# M700A.net
KiCad netlist of a schematic drawn in EAGLE
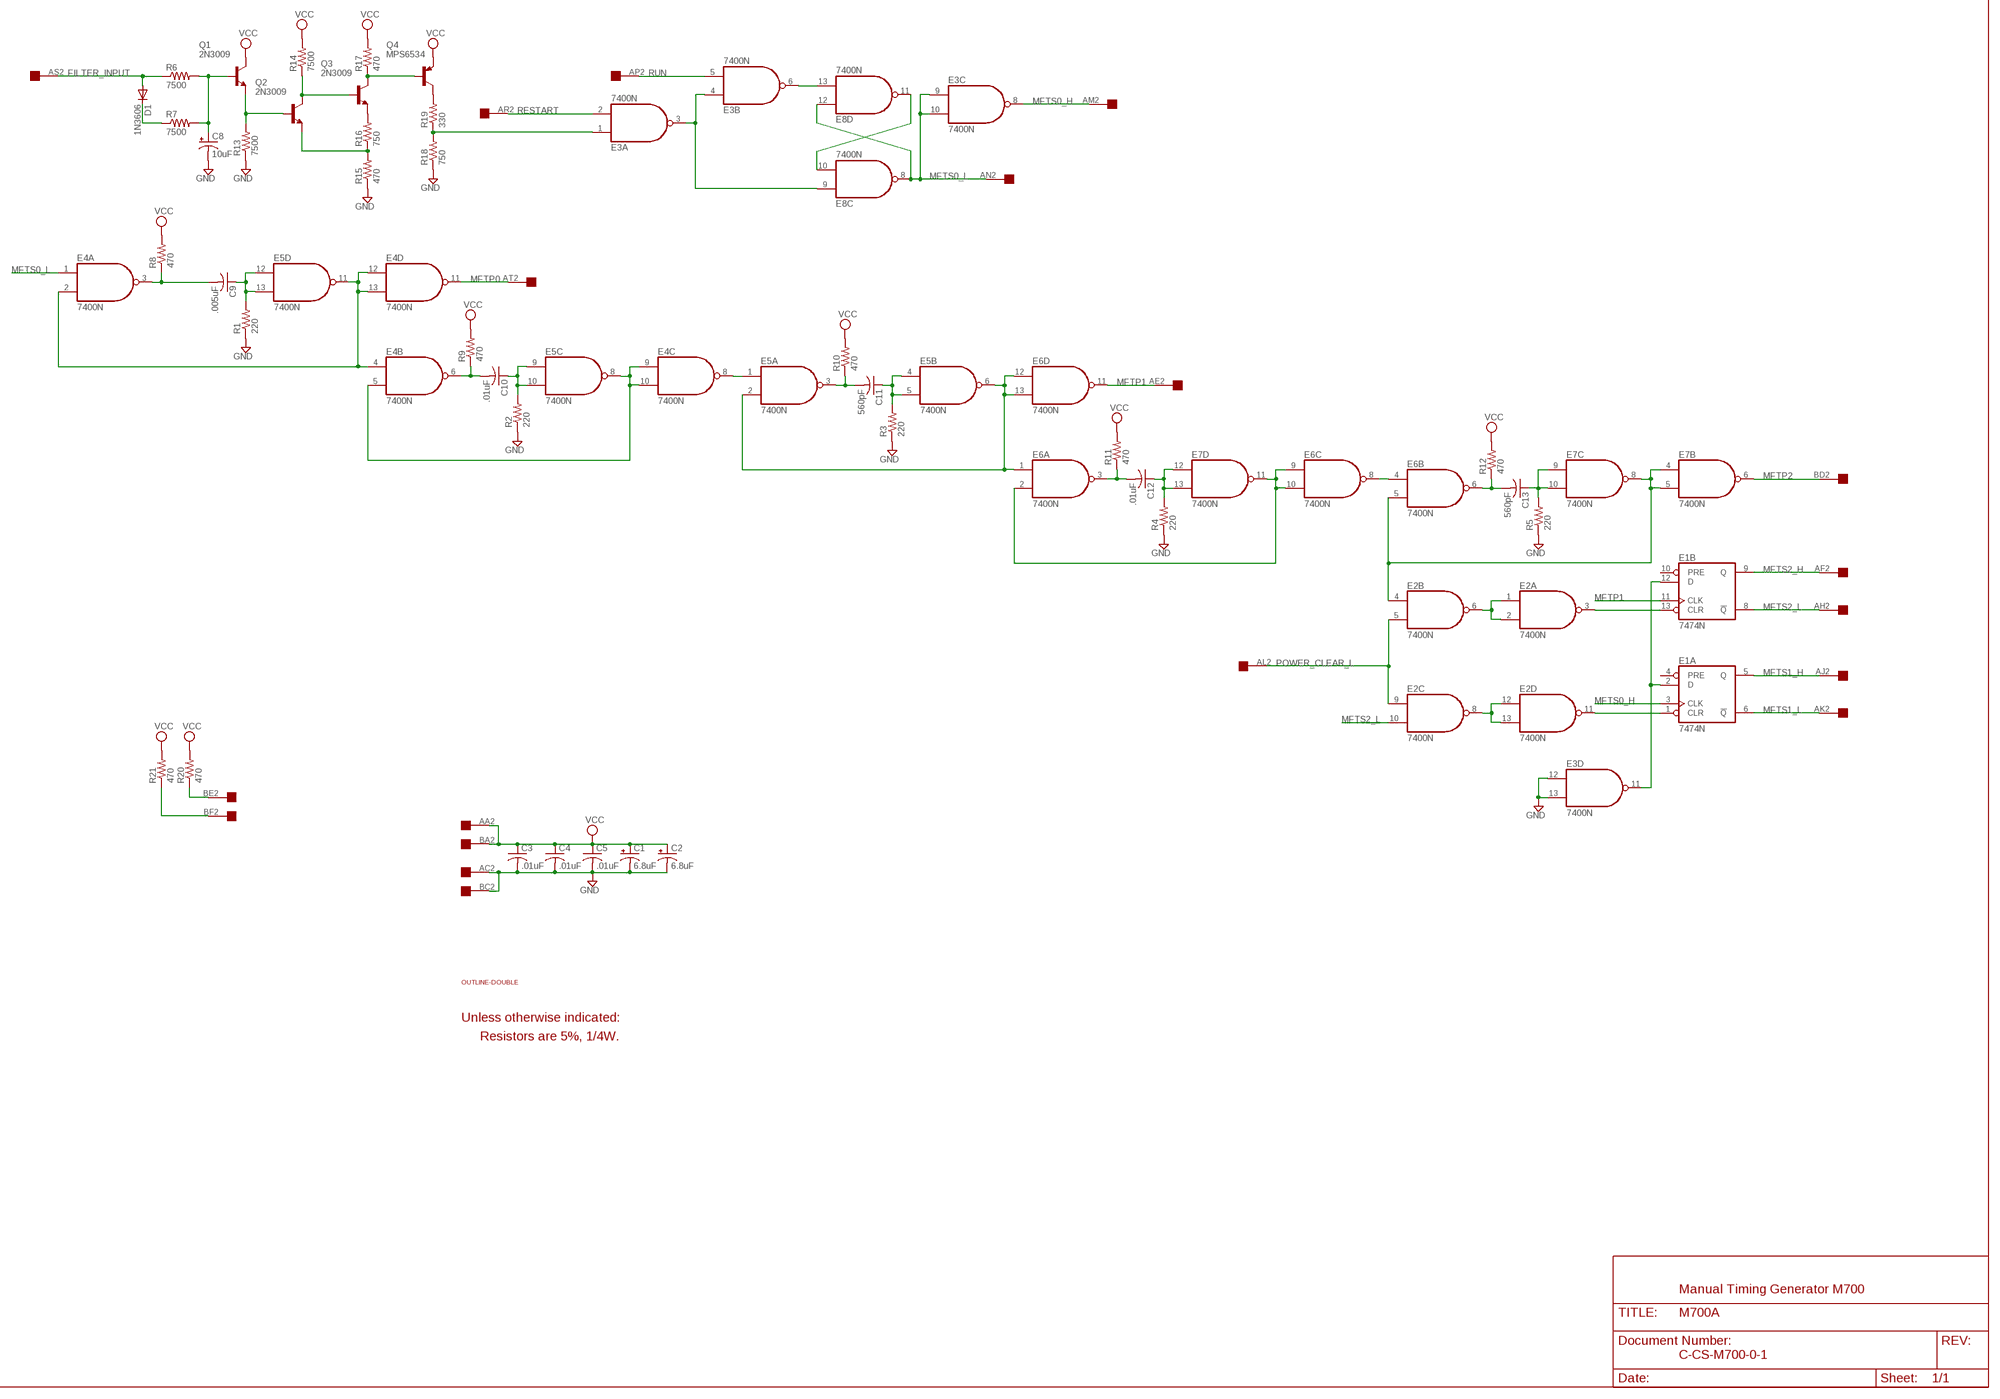
[diagram p0: schematic, sheet 1]

(export (version "E")
  (design (tool "Eeschema 10.0.6"))
  (components
    (comp (ref "C1")
      (value "6.8uF")
      (footprint "eagle-import:E15-5")
      (libsource (lib "eagle-import") (part "CPOL-USE15-5AXIAL"))
    )
    (comp (ref "C2")
      (value "6.8uF")
      (footprint "eagle-import:E15-5")
      (libsource (lib "eagle-import") (part "CPOL-USE15-5AXIAL"))
    )
    (comp (ref "C3")
      (value ".01uF")
      (footprint "eagle-import:C050-025X075")
      (libsource (lib "eagle-import") (part "C-US050-025X075"))
    )
    (comp (ref "C4")
      (value ".01uF")
      (footprint "eagle-import:C050-025X075")
      (libsource (lib "eagle-import") (part "C-US050-025X075"))
    )
    (comp (ref "C5")
      (value ".01uF")
      (footprint "eagle-import:C050-025X075")
      (libsource (lib "eagle-import") (part "C-US050-025X075"))
    )
    (comp (ref "C8")
      (value "10uF")
      (footprint "eagle-import:E15-5")
      (libsource (lib "eagle-import") (part "CPOL-USE15-5AXIAL"))
    )
    (comp (ref "C9")
      (value ".005uF")
      (footprint "eagle-import:C050-025X075")
      (libsource (lib "eagle-import") (part "C-US050-025X075"))
    )
    (comp (ref "C10")
      (value ".01uF")
      (footprint "eagle-import:C050-025X075")
      (libsource (lib "eagle-import") (part "C-US050-025X075"))
    )
    (comp (ref "C11")
      (value "560pF")
      (footprint "eagle-import:C050-025X075")
      (libsource (lib "eagle-import") (part "C-US050-025X075"))
    )
    (comp (ref "C12")
      (value ".01uF")
      (footprint "eagle-import:C050-025X075")
      (libsource (lib "eagle-import") (part "C-US050-025X075"))
    )
    (comp (ref "C13")
      (value "560pF")
      (footprint "eagle-import:C050-025X075")
      (libsource (lib "eagle-import") (part "C-US050-025X075"))
    )
    (comp (ref "D1")
      (value "1N3606")
      (footprint "eagle-import:DO35-10")
      (libsource (lib "eagle-import") (part "1N4148DO35-10"))
    )
    (comp (ref "E1")
      (value "7474N")
      (footprint "eagle-import:DIL14")
      (libsource (lib "eagle-import") (part "7474NS"))
    )
    (comp (ref "E2")
      (value "7400N")
      (footprint "eagle-import:DIL14")
      (libsource (lib "eagle-import") (part "7400N"))
    )
    (comp (ref "E3")
      (value "7400N")
      (footprint "eagle-import:DIL14")
      (libsource (lib "eagle-import") (part "7400N"))
    )
    (comp (ref "E4")
      (value "7400N")
      (footprint "eagle-import:DIL14")
      (libsource (lib "eagle-import") (part "7400N"))
    )
    (comp (ref "E5")
      (value "7400N")
      (footprint "eagle-import:DIL14")
      (libsource (lib "eagle-import") (part "7400N"))
    )
    (comp (ref "E6")
      (value "7400N")
      (footprint "eagle-import:DIL14")
      (libsource (lib "eagle-import") (part "7400N"))
    )
    (comp (ref "E7")
      (value "7400N")
      (footprint "eagle-import:DIL14")
      (libsource (lib "eagle-import") (part "7400N"))
    )
    (comp (ref "E8")
      (value "7400N")
      (footprint "eagle-import:DIL14")
      (libsource (lib "eagle-import") (part "7400N"))
    )
    (comp (ref "Q1")
      (value "2N3009")
      (footprint "eagle-import:TO5")
      (libsource (lib "eagle-import") (part "2N2102"))
    )
    (comp (ref "Q2")
      (value "2N3009")
      (footprint "eagle-import:TO5")
      (libsource (lib "eagle-import") (part "2N2102"))
    )
    (comp (ref "Q3")
      (value "2N3009")
      (footprint "eagle-import:TO5")
      (libsource (lib "eagle-import") (part "2N2102"))
    )
    (comp (ref "Q4")
      (value "MPS6534")
      (footprint "eagle-import:TO5")
      (libsource (lib "eagle-import") (part "2N2905"))
    )
    (comp (ref "R1")
      (value "220")
      (footprint "eagle-import:0207_10")
      (libsource (lib "eagle-import") (part "R-US_0207/10"))
    )
    (comp (ref "R2")
      (value "220")
      (footprint "eagle-import:0207_10")
      (libsource (lib "eagle-import") (part "R-US_0207/10"))
    )
    (comp (ref "R3")
      (value "220")
      (footprint "eagle-import:0207_10")
      (libsource (lib "eagle-import") (part "R-US_0207/10"))
    )
    (comp (ref "R4")
      (value "220")
      (footprint "eagle-import:0207_10")
      (libsource (lib "eagle-import") (part "R-US_0207/10"))
    )
    (comp (ref "R5")
      (value "220")
      (footprint "eagle-import:0207_10")
      (libsource (lib "eagle-import") (part "R-US_0207/10"))
    )
    (comp (ref "R6")
      (value "7500")
      (footprint "eagle-import:0207_10")
      (libsource (lib "eagle-import") (part "R-US_0207/10"))
    )
    (comp (ref "R7")
      (value "7500")
      (footprint "eagle-import:0207_10")
      (libsource (lib "eagle-import") (part "R-US_0207/10"))
    )
    (comp (ref "R8")
      (value "470")
      (footprint "eagle-import:0207_10")
      (libsource (lib "eagle-import") (part "R-US_0207/10"))
    )
    (comp (ref "R9")
      (value "470")
      (footprint "eagle-import:0207_10")
      (libsource (lib "eagle-import") (part "R-US_0207/10"))
    )
    (comp (ref "R10")
      (value "470")
      (footprint "eagle-import:0207_10")
      (libsource (lib "eagle-import") (part "R-US_0207/10"))
    )
    (comp (ref "R11")
      (value "470")
      (footprint "eagle-import:0207_10")
      (libsource (lib "eagle-import") (part "R-US_0207/10"))
    )
    (comp (ref "R12")
      (value "470")
      (footprint "eagle-import:0207_10")
      (libsource (lib "eagle-import") (part "R-US_0207/10"))
    )
    (comp (ref "R13")
      (value "7500")
      (footprint "eagle-import:0207_10")
      (libsource (lib "eagle-import") (part "R-US_0207/10"))
    )
    (comp (ref "R14")
      (value "7500")
      (footprint "eagle-import:0207_10")
      (libsource (lib "eagle-import") (part "R-US_0207/10"))
    )
    (comp (ref "R15")
      (value "470")
      (footprint "eagle-import:0207_10")
      (libsource (lib "eagle-import") (part "R-US_0207/10"))
    )
    (comp (ref "R16")
      (value "750")
      (footprint "eagle-import:0207_10")
      (libsource (lib "eagle-import") (part "R-US_0207/10"))
    )
    (comp (ref "R17")
      (value "470")
      (footprint "eagle-import:0207_10")
      (libsource (lib "eagle-import") (part "R-US_0207/10"))
    )
    (comp (ref "R18")
      (value "750")
      (footprint "eagle-import:0207_10")
      (libsource (lib "eagle-import") (part "R-US_0207/10"))
    )
    (comp (ref "R19")
      (value "330")
      (footprint "eagle-import:0207_10")
      (libsource (lib "eagle-import") (part "R-US_0207/10"))
    )
    (comp (ref "R20")
      (value "470")
      (footprint "eagle-import:0207_10")
      (libsource (lib "eagle-import") (part "R-US_0207/10"))
    )
    (comp (ref "R21")
      (value "470")
      (footprint "eagle-import:0207_10")
      (libsource (lib "eagle-import") (part "R-US_0207/10"))
    )
    (comp (ref "U$1")
      (value "DOUBLE")
      (footprint "eagle-import:EDGE-CON4")
      (libsource (lib "eagle-import") (part "DOUBLE"))
    )
    (comp (ref "U$2")
      (value "OUTLINE-DOUBLE")
      (footprint "eagle-import:DOUBLE")
      (libsource (lib "eagle-import") (part "OUTLINE-DOUBLE"))
    )
  )
  (nets
    (net (code "1") (name "/FILTER_INPUT") (class "Default")
      (node (ref "D1") (pin "A") (pinfunction "A_A") (pintype "passive"))
      (node (ref "R6") (pin "1") (pinfunction "1_1") (pintype "passive"))
      (node (ref "U$1") (pin "AS2") (pinfunction "1_AS2") (pintype "bidirectional"))
    )
    (net (code "2") (name "/MFTP0") (class "Default")
      (node (ref "E4") (pin "11") (pinfunction "O_11") (pintype "output"))
      (node (ref "U$1") (pin "AT2") (pinfunction "1_AT2") (pintype "bidirectional"))
    )
    (net (code "3") (name "/MFTP1") (class "Default")
      (node (ref "E1") (pin "11") (pinfunction "CLK_11") (pintype "input"))
      (node (ref "E6") (pin "11") (pinfunction "O_11") (pintype "output"))
      (node (ref "U$1") (pin "AE2") (pinfunction "1_AE2") (pintype "bidirectional"))
    )
    (net (code "4") (name "/MFTP2") (class "Default")
      (node (ref "E7") (pin "6") (pinfunction "O_6") (pintype "output"))
      (node (ref "U$1") (pin "BD2") (pinfunction "1_BD2") (pintype "bidirectional"))
    )
    (net (code "5") (name "/MFTS0_H") (class "Default")
      (node (ref "E1") (pin "3") (pinfunction "CLK_3") (pintype "input"))
      (node (ref "E3") (pin "8") (pinfunction "O_8") (pintype "output"))
      (node (ref "U$1") (pin "AM2") (pinfunction "1_AM2") (pintype "bidirectional"))
    )
    (net (code "6") (name "/MFTS0_L") (class "Default")
      (node (ref "E3") (pin "10") (pinfunction "I1_10") (pintype "input"))
      (node (ref "E3") (pin "9") (pinfunction "I0_9") (pintype "input"))
      (node (ref "E4") (pin "1") (pinfunction "I0_1") (pintype "input"))
      (node (ref "E8") (pin "12") (pinfunction "I0_12") (pintype "input"))
      (node (ref "E8") (pin "8") (pinfunction "O_8") (pintype "output"))
      (node (ref "U$1") (pin "AN2") (pinfunction "1_AN2") (pintype "bidirectional"))
    )
    (net (code "7") (name "/MFTS1_H") (class "Default")
      (node (ref "E1") (pin "5") (pinfunction "Q_5") (pintype "output"))
      (node (ref "U$1") (pin "AJ2") (pinfunction "1_AJ2") (pintype "bidirectional"))
    )
    (net (code "8") (name "/MFTS1_L") (class "Default")
      (node (ref "E1") (pin "6") (pinfunction "~{Q}_6") (pintype "output"))
      (node (ref "U$1") (pin "AK2") (pinfunction "1_AK2") (pintype "bidirectional"))
    )
    (net (code "9") (name "/MFTS2_H") (class "Default")
      (node (ref "E1") (pin "9") (pinfunction "Q_9") (pintype "output"))
      (node (ref "U$1") (pin "AF2") (pinfunction "1_AF2") (pintype "bidirectional"))
    )
    (net (code "10") (name "/MFTS2_L") (class "Default")
      (node (ref "E1") (pin "8") (pinfunction "~{Q}_8") (pintype "output"))
      (node (ref "E2") (pin "10") (pinfunction "I1_10") (pintype "input"))
      (node (ref "U$1") (pin "AH2") (pinfunction "1_AH2") (pintype "bidirectional"))
    )
    (net (code "11") (name "/POWER_CLEAR_L") (class "Default")
      (node (ref "E2") (pin "5") (pinfunction "I1_5") (pintype "input"))
      (node (ref "E2") (pin "9") (pinfunction "I0_9") (pintype "input"))
      (node (ref "U$1") (pin "AL2") (pinfunction "1_AL2") (pintype "bidirectional"))
    )
    (net (code "12") (name "/RESTART") (class "Default")
      (node (ref "E3") (pin "2") (pinfunction "I1_2") (pintype "input"))
      (node (ref "U$1") (pin "AR2") (pinfunction "1_AR2") (pintype "bidirectional"))
    )
    (net (code "13") (name "/RUN") (class "Default")
      (node (ref "E3") (pin "5") (pinfunction "I1_5") (pintype "input"))
      (node (ref "U$1") (pin "AP2") (pinfunction "1_AP2") (pintype "bidirectional"))
    )
    (net (code "14") (name "GND") (class "Default")
      (node (ref "C1") (pin "-") (pinfunction "-_-") (pintype "passive"))
      (node (ref "C2") (pin "-") (pinfunction "-_-") (pintype "passive"))
      (node (ref "C3") (pin "2") (pinfunction "2_2") (pintype "passive"))
      (node (ref "C4") (pin "2") (pinfunction "2_2") (pintype "passive"))
      (node (ref "C5") (pin "2") (pinfunction "2_2") (pintype "passive"))
      (node (ref "C8") (pin "-") (pinfunction "-_-") (pintype "passive"))
      (node (ref "E3") (pin "12") (pinfunction "I0_12") (pintype "input"))
      (node (ref "E3") (pin "13") (pinfunction "I1_13") (pintype "input"))
      (node (ref "R1") (pin "1") (pinfunction "1_1") (pintype "passive"))
      (node (ref "R13") (pin "1") (pinfunction "1_1") (pintype "passive"))
      (node (ref "R15") (pin "1") (pinfunction "1_1") (pintype "passive"))
      (node (ref "R18") (pin "1") (pinfunction "1_1") (pintype "passive"))
      (node (ref "R2") (pin "1") (pinfunction "1_1") (pintype "passive"))
      (node (ref "R3") (pin "1") (pinfunction "1_1") (pintype "passive"))
      (node (ref "R4") (pin "1") (pinfunction "1_1") (pintype "passive"))
      (node (ref "R5") (pin "1") (pinfunction "1_1") (pintype "passive"))
      (node (ref "U$1") (pin "AC2") (pinfunction "1_AC2") (pintype "bidirectional"))
      (node (ref "U$1") (pin "BC2") (pinfunction "1_BC2") (pintype "bidirectional"))
    )
    (net (code "15") (name "Net-(D1-PadC)") (class "Default")
      (node (ref "D1") (pin "C") (pinfunction "C_C") (pintype "passive"))
      (node (ref "R7") (pin "1") (pinfunction "1_1") (pintype "passive"))
    )
    (net (code "16") (name "Net-(E1A-CLR)") (class "Default")
      (node (ref "E1") (pin "1") (pinfunction "CLR_1") (pintype "input"))
      (node (ref "E2") (pin "11") (pinfunction "O_11") (pintype "output"))
    )
    (net (code "17") (name "Net-(E1A-D)") (class "Default")
      (node (ref "E1") (pin "12") (pinfunction "D_12") (pintype "input"))
      (node (ref "E1") (pin "2") (pinfunction "D_2") (pintype "input"))
      (node (ref "E3") (pin "11") (pinfunction "O_11") (pintype "output"))
    )
    (net (code "18") (name "Net-(E1B-CLR)") (class "Default")
      (node (ref "E1") (pin "13") (pinfunction "CLR_13") (pintype "input"))
      (node (ref "E2") (pin "3") (pinfunction "O_3") (pintype "output"))
    )
    (net (code "19") (name "Net-(E2A-I0)") (class "Default")
      (node (ref "E2") (pin "1") (pinfunction "I0_1") (pintype "input"))
      (node (ref "E2") (pin "2") (pinfunction "I1_2") (pintype "input"))
      (node (ref "E2") (pin "6") (pinfunction "O_6") (pintype "output"))
    )
    (net (code "20") (name "Net-(E2B-I0)") (class "Default")
      (node (ref "E2") (pin "4") (pinfunction "I0_4") (pintype "input"))
      (node (ref "E6") (pin "5") (pinfunction "I1_5") (pintype "input"))
      (node (ref "E7") (pin "4") (pinfunction "I0_4") (pintype "input"))
      (node (ref "E7") (pin "5") (pinfunction "I1_5") (pintype "input"))
      (node (ref "E7") (pin "8") (pinfunction "O_8") (pintype "output"))
    )
    (net (code "21") (name "Net-(E2C-O)") (class "Default")
      (node (ref "E2") (pin "12") (pinfunction "I0_12") (pintype "input"))
      (node (ref "E2") (pin "13") (pinfunction "I1_13") (pintype "input"))
      (node (ref "E2") (pin "8") (pinfunction "O_8") (pintype "output"))
    )
    (net (code "22") (name "Net-(E3A-I0)") (class "Default")
      (node (ref "E3") (pin "1") (pinfunction "I0_1") (pintype "input"))
      (node (ref "R18") (pin "2") (pinfunction "2_2") (pintype "passive"))
      (node (ref "R19") (pin "1") (pinfunction "1_1") (pintype "passive"))
    )
    (net (code "23") (name "Net-(E3A-O)") (class "Default")
      (node (ref "E3") (pin "3") (pinfunction "O_3") (pintype "output"))
      (node (ref "E3") (pin "4") (pinfunction "I0_4") (pintype "input"))
      (node (ref "E8") (pin "9") (pinfunction "I0_9") (pintype "input"))
    )
    (net (code "24") (name "Net-(E3B-O)") (class "Default")
      (node (ref "E3") (pin "6") (pinfunction "O_6") (pintype "output"))
      (node (ref "E8") (pin "13") (pinfunction "I1_13") (pintype "input"))
    )
    (net (code "25") (name "Net-(E4A-I1)") (class "Default")
      (node (ref "E4") (pin "12") (pinfunction "I0_12") (pintype "input"))
      (node (ref "E4") (pin "13") (pinfunction "I1_13") (pintype "input"))
      (node (ref "E4") (pin "2") (pinfunction "I1_2") (pintype "input"))
      (node (ref "E4") (pin "4") (pinfunction "I0_4") (pintype "input"))
      (node (ref "E5") (pin "11") (pinfunction "O_11") (pintype "output"))
    )
    (net (code "26") (name "Net-(E4A-O)") (class "Default")
      (node (ref "C9") (pin "2") (pinfunction "2_2") (pintype "passive"))
      (node (ref "E4") (pin "3") (pinfunction "O_3") (pintype "output"))
      (node (ref "R8") (pin "1") (pinfunction "1_1") (pintype "passive"))
    )
    (net (code "27") (name "Net-(E4B-I1)") (class "Default")
      (node (ref "E4") (pin "10") (pinfunction "I1_10") (pintype "input"))
      (node (ref "E4") (pin "5") (pinfunction "I1_5") (pintype "input"))
      (node (ref "E4") (pin "9") (pinfunction "I0_9") (pintype "input"))
      (node (ref "E5") (pin "8") (pinfunction "O_8") (pintype "output"))
    )
    (net (code "28") (name "Net-(E4B-O)") (class "Default")
      (node (ref "C10") (pin "2") (pinfunction "2_2") (pintype "passive"))
      (node (ref "E4") (pin "6") (pinfunction "O_6") (pintype "output"))
      (node (ref "R9") (pin "1") (pinfunction "1_1") (pintype "passive"))
    )
    (net (code "29") (name "Net-(E4C-O)") (class "Default")
      (node (ref "E4") (pin "8") (pinfunction "O_8") (pintype "output"))
      (node (ref "E5") (pin "1") (pinfunction "I0_1") (pintype "input"))
    )
    (net (code "30") (name "Net-(E5A-I1)") (class "Default")
      (node (ref "E5") (pin "2") (pinfunction "I1_2") (pintype "input"))
      (node (ref "E5") (pin "6") (pinfunction "O_6") (pintype "output"))
      (node (ref "E6") (pin "1") (pinfunction "I0_1") (pintype "input"))
      (node (ref "E6") (pin "12") (pinfunction "I0_12") (pintype "input"))
      (node (ref "E6") (pin "13") (pinfunction "I1_13") (pintype "input"))
    )
    (net (code "31") (name "Net-(E5A-O)") (class "Default")
      (node (ref "C11") (pin "2") (pinfunction "2_2") (pintype "passive"))
      (node (ref "E5") (pin "3") (pinfunction "O_3") (pintype "output"))
      (node (ref "R10") (pin "1") (pinfunction "1_1") (pintype "passive"))
    )
    (net (code "32") (name "Net-(E5B-I0)") (class "Default")
      (node (ref "C11") (pin "1") (pinfunction "1_1") (pintype "passive"))
      (node (ref "E5") (pin "4") (pinfunction "I0_4") (pintype "input"))
      (node (ref "E5") (pin "5") (pinfunction "I1_5") (pintype "input"))
      (node (ref "R3") (pin "2") (pinfunction "2_2") (pintype "passive"))
    )
    (net (code "33") (name "Net-(E5C-I0)") (class "Default")
      (node (ref "C10") (pin "1") (pinfunction "1_1") (pintype "passive"))
      (node (ref "E5") (pin "10") (pinfunction "I1_10") (pintype "input"))
      (node (ref "E5") (pin "9") (pinfunction "I0_9") (pintype "input"))
      (node (ref "R2") (pin "2") (pinfunction "2_2") (pintype "passive"))
    )
    (net (code "34") (name "Net-(E5D-I0)") (class "Default")
      (node (ref "C9") (pin "1") (pinfunction "1_1") (pintype "passive"))
      (node (ref "E5") (pin "12") (pinfunction "I0_12") (pintype "input"))
      (node (ref "E5") (pin "13") (pinfunction "I1_13") (pintype "input"))
      (node (ref "R1") (pin "2") (pinfunction "2_2") (pintype "passive"))
    )
    (net (code "35") (name "Net-(E6A-I1)") (class "Default")
      (node (ref "E6") (pin "10") (pinfunction "I1_10") (pintype "input"))
      (node (ref "E6") (pin "2") (pinfunction "I1_2") (pintype "input"))
      (node (ref "E6") (pin "9") (pinfunction "I0_9") (pintype "input"))
      (node (ref "E7") (pin "11") (pinfunction "O_11") (pintype "output"))
    )
    (net (code "36") (name "Net-(E6A-O)") (class "Default")
      (node (ref "C12") (pin "2") (pinfunction "2_2") (pintype "passive"))
      (node (ref "E6") (pin "3") (pinfunction "O_3") (pintype "output"))
      (node (ref "R11") (pin "1") (pinfunction "1_1") (pintype "passive"))
    )
    (net (code "37") (name "Net-(E6B-I0)") (class "Default")
      (node (ref "E6") (pin "4") (pinfunction "I0_4") (pintype "input"))
      (node (ref "E6") (pin "8") (pinfunction "O_8") (pintype "output"))
    )
    (net (code "38") (name "Net-(E6B-O)") (class "Default")
      (node (ref "C13") (pin "2") (pinfunction "2_2") (pintype "passive"))
      (node (ref "E6") (pin "6") (pinfunction "O_6") (pintype "output"))
      (node (ref "R12") (pin "1") (pinfunction "1_1") (pintype "passive"))
    )
    (net (code "39") (name "Net-(E7C-I0)") (class "Default")
      (node (ref "C13") (pin "1") (pinfunction "1_1") (pintype "passive"))
      (node (ref "E7") (pin "10") (pinfunction "I1_10") (pintype "input"))
      (node (ref "E7") (pin "9") (pinfunction "I0_9") (pintype "input"))
      (node (ref "R5") (pin "2") (pinfunction "2_2") (pintype "passive"))
    )
    (net (code "40") (name "Net-(E7D-I0)") (class "Default")
      (node (ref "C12") (pin "1") (pinfunction "1_1") (pintype "passive"))
      (node (ref "E7") (pin "12") (pinfunction "I0_12") (pintype "input"))
      (node (ref "E7") (pin "13") (pinfunction "I1_13") (pintype "input"))
      (node (ref "R4") (pin "2") (pinfunction "2_2") (pintype "passive"))
    )
    (net (code "41") (name "Net-(E8C-I1)") (class "Default")
      (node (ref "E8") (pin "10") (pinfunction "I1_10") (pintype "input"))
      (node (ref "E8") (pin "11") (pinfunction "O_11") (pintype "output"))
    )
    (net (code "42") (name "Net-(Q1-B)") (class "Default")
      (node (ref "C8") (pin "+") (pinfunction "+_+") (pintype "passive"))
      (node (ref "Q1") (pin "2") (pinfunction "B_2") (pintype "passive"))
      (node (ref "R6") (pin "2") (pinfunction "2_2") (pintype "passive"))
      (node (ref "R7") (pin "2") (pinfunction "2_2") (pintype "passive"))
    )
    (net (code "43") (name "Net-(Q1-E)") (class "Default")
      (node (ref "Q1") (pin "1") (pinfunction "E_1") (pintype "passive"))
      (node (ref "Q2") (pin "2") (pinfunction "B_2") (pintype "passive"))
      (node (ref "R13") (pin "2") (pinfunction "2_2") (pintype "passive"))
    )
    (net (code "44") (name "Net-(Q2-C)") (class "Default")
      (node (ref "Q2") (pin "3") (pinfunction "C_3") (pintype "passive"))
      (node (ref "Q3") (pin "2") (pinfunction "B_2") (pintype "passive"))
      (node (ref "R14") (pin "1") (pinfunction "1_1") (pintype "passive"))
    )
    (net (code "45") (name "Net-(Q2-E)") (class "Default")
      (node (ref "Q2") (pin "1") (pinfunction "E_1") (pintype "passive"))
      (node (ref "R15") (pin "2") (pinfunction "2_2") (pintype "passive"))
      (node (ref "R16") (pin "1") (pinfunction "1_1") (pintype "passive"))
    )
    (net (code "46") (name "Net-(Q3-C)") (class "Default")
      (node (ref "Q3") (pin "3") (pinfunction "C_3") (pintype "passive"))
      (node (ref "Q4") (pin "2") (pinfunction "B_2") (pintype "passive"))
      (node (ref "R17") (pin "1") (pinfunction "1_1") (pintype "passive"))
    )
    (net (code "47") (name "Net-(Q3-E)") (class "Default")
      (node (ref "Q3") (pin "1") (pinfunction "E_1") (pintype "passive"))
      (node (ref "R16") (pin "2") (pinfunction "2_2") (pintype "passive"))
    )
    (net (code "48") (name "Net-(Q4-C)") (class "Default")
      (node (ref "Q4") (pin "3") (pinfunction "C_3") (pintype "passive"))
      (node (ref "R19") (pin "2") (pinfunction "2_2") (pintype "passive"))
    )
    (net (code "49") (name "Net-(U$1AT-1)") (class "Default")
      (node (ref "R20") (pin "1") (pinfunction "1_1") (pintype "passive"))
      (node (ref "U$1") (pin "BE2") (pinfunction "1_BE2") (pintype "bidirectional"))
    )
    (net (code "50") (name "Net-(U$1AV-1)") (class "Default")
      (node (ref "R21") (pin "1") (pinfunction "1_1") (pintype "passive"))
      (node (ref "U$1") (pin "BF2") (pinfunction "1_BF2") (pintype "bidirectional"))
    )
    (net (code "51") (name "VCC") (class "Default")
      (node (ref "C1") (pin "+") (pinfunction "+_+") (pintype "passive"))
      (node (ref "C2") (pin "+") (pinfunction "+_+") (pintype "passive"))
      (node (ref "C3") (pin "1") (pinfunction "1_1") (pintype "passive"))
      (node (ref "C4") (pin "1") (pinfunction "1_1") (pintype "passive"))
      (node (ref "C5") (pin "1") (pinfunction "1_1") (pintype "passive"))
      (node (ref "Q1") (pin "3") (pinfunction "C_3") (pintype "passive"))
      (node (ref "Q4") (pin "1") (pinfunction "E_1") (pintype "passive"))
      (node (ref "R10") (pin "2") (pinfunction "2_2") (pintype "passive"))
      (node (ref "R11") (pin "2") (pinfunction "2_2") (pintype "passive"))
      (node (ref "R12") (pin "2") (pinfunction "2_2") (pintype "passive"))
      (node (ref "R14") (pin "2") (pinfunction "2_2") (pintype "passive"))
      (node (ref "R17") (pin "2") (pinfunction "2_2") (pintype "passive"))
      (node (ref "R20") (pin "2") (pinfunction "2_2") (pintype "passive"))
      (node (ref "R21") (pin "2") (pinfunction "2_2") (pintype "passive"))
      (node (ref "R8") (pin "2") (pinfunction "2_2") (pintype "passive"))
      (node (ref "R9") (pin "2") (pinfunction "2_2") (pintype "passive"))
      (node (ref "U$1") (pin "AA2") (pinfunction "1_AA2") (pintype "bidirectional"))
      (node (ref "U$1") (pin "BA2") (pinfunction "1_BA2") (pintype "bidirectional"))
    )
    (net (code "52") (name "unconnected-(E1A-PRE-Pad4)") (class "Default")
      (node (ref "E1") (pin "4") (pinfunction "PRE_4") (pintype "input"))
    )
    (net (code "53") (name "unconnected-(E1B-PRE-Pad10)") (class "Default")
      (node (ref "E1") (pin "10") (pinfunction "PRE_10") (pintype "input"))
    )
  )
)
